# Sensors-V1_1.net
KiCad netlist of a schematic drawn in EAGLE
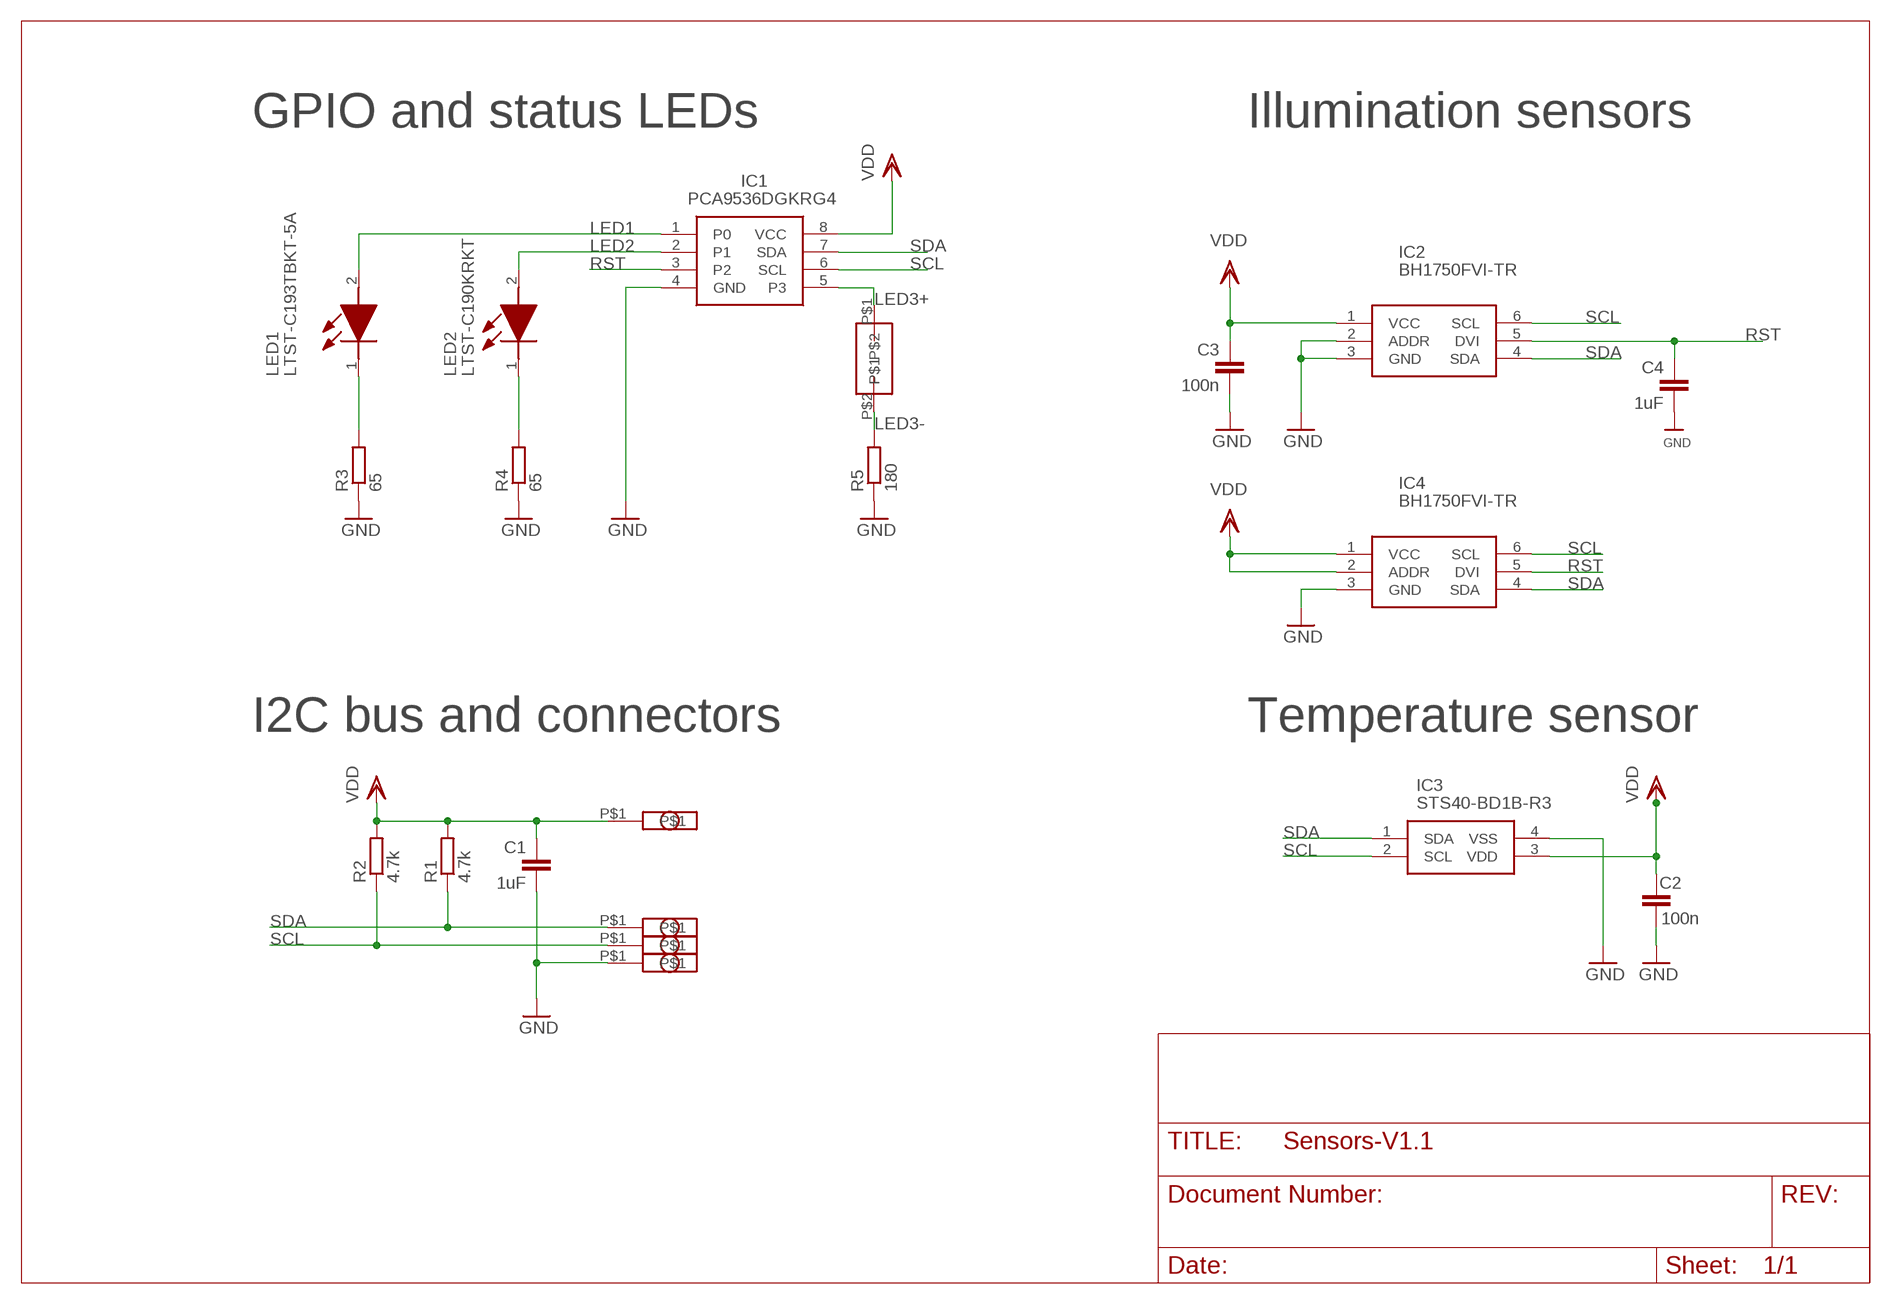
[diagram p0: schematic, sheet 1]

(export (version "E")
  (design (tool "Eeschema 10.0.6"))
  (components
    (comp (ref "C1")
      (value "1uF")
      (footprint "eagle-import:C0603")
      (libsource (lib "eagle-import") (part "C-EUC0603"))
    )
    (comp (ref "C2")
      (value "100n")
      (footprint "eagle-import:C0603")
      (libsource (lib "eagle-import") (part "C-EUC0603"))
    )
    (comp (ref "C3")
      (value "100n")
      (footprint "eagle-import:C0603")
      (libsource (lib "eagle-import") (part "C-EUC0603"))
    )
    (comp (ref "C4")
      (value "1uF")
      (footprint "eagle-import:C0603")
      (libsource (lib "eagle-import") (part "C-EUC0603"))
    )
    (comp (ref "IC1")
      (value "PCA9536DGKRG4")
      (footprint "eagle-import:SOP65P490X110-8N")
      (fields (field (name "MOUSER_PART_NUMBER") "595-PCA9536DGKRG4"))
      (libsource (lib "eagle-import") (part "PCA9536DGKRG4"))
    )
    (comp (ref "IC2")
      (value "BH1750FVI-TR")
      (footprint "eagle-import:WSOF6")
      (libsource (lib "eagle-import") (part "BH1750FVI-TR"))
    )
    (comp (ref "IC3")
      (value "STS40-BD1B-R3")
      (footprint "eagle-import:STS40BD1BR3")
      (fields (field (name "MOUSER_PART_NUMBER") "403-STS40-BD1B-R3"))
      (libsource (lib "eagle-import") (part "STS40-BD1B-R3"))
    )
    (comp (ref "IC4")
      (value "BH1750FVI-TR")
      (footprint "eagle-import:WSOF6")
      (libsource (lib "eagle-import") (part "BH1750FVI-TR"))
    )
    (comp (ref "LED1")
      (value "LTST-C193TBKT-5A")
      (footprint "eagle-import:LEDC1608X45N")
      (fields (field (name "MOUSER_PART_NUMBER") "859-LTSTC193TBKT5A"))
      (libsource (lib "eagle-import") (part "LTST-C193TBKT-5A"))
    )
    (comp (ref "LED2")
      (value "LTST-C190KRKT")
      (footprint "eagle-import:LEDC1607X80N")
      (fields
        (field (name "MANUFACTURER_PART_NUMBER") "LTST-C190KFKT")
        (field (name "MOUSER_PART_NUMBER") "859-LTST-C190KFKT")
      )
      (libsource (lib "eagle-import") (part "LTST-C190KFKT"))
    )
    (comp (ref "R1")
      (value "4.7k")
      (footprint "eagle-import:R0603")
      (libsource (lib "eagle-import") (part "R_JLMR0603"))
    )
    (comp (ref "R2")
      (value "4.7k")
      (footprint "eagle-import:R0603")
      (libsource (lib "eagle-import") (part "R_JLMR0603"))
    )
    (comp (ref "R3")
      (value "65")
      (footprint "eagle-import:R0603")
      (libsource (lib "eagle-import") (part "R_JLMR0603"))
    )
    (comp (ref "R4")
      (value "65")
      (footprint "eagle-import:R0603")
      (libsource (lib "eagle-import") (part "R_JLMR0603"))
    )
    (comp (ref "R5")
      (value "180")
      (footprint "eagle-import:R0603")
      (libsource (lib "eagle-import") (part "R_JLMR0603"))
    )
    (comp (ref "U$1")
      (value "PADL8")
      (footprint "eagle-import:PAD-8")
      (libsource (lib "eagle-import") (part "PADL8"))
    )
    (comp (ref "U$2")
      (value "PADL8")
      (footprint "eagle-import:PAD-8")
      (libsource (lib "eagle-import") (part "PADL8"))
    )
    (comp (ref "U$3")
      (value "PADL8")
      (footprint "eagle-import:PAD-8")
      (libsource (lib "eagle-import") (part "PADL8"))
    )
    (comp (ref "U$4")
      (value "PADL8")
      (footprint "eagle-import:PAD-8")
      (libsource (lib "eagle-import") (part "PADL8"))
    )
    (comp (ref "U$5")
      (value "LEDPINS")
      (footprint "eagle-import:LEDPINS254")
      (libsource (lib "eagle-import") (part "LEDPINS"))
    )
  )
  (nets
    (net (code "1") (name "/LED1") (class "Default")
      (node (ref "IC1") (pin "1") (pinfunction "P0_1") (pintype "bidirectional"))
      (node (ref "LED1") (pin "2") (pinfunction "A_2") (pintype "bidirectional"))
    )
    (net (code "2") (name "/LED2") (class "Default")
      (node (ref "IC1") (pin "2") (pinfunction "P1_2") (pintype "bidirectional"))
      (node (ref "LED2") (pin "2") (pinfunction "A_2") (pintype "bidirectional"))
    )
    (net (code "3") (name "/LED3+") (class "Default")
      (node (ref "IC1") (pin "5") (pinfunction "P3_5") (pintype "bidirectional"))
      (node (ref "U$5") (pin "P$1") (pinfunction "P$1_P$1") (pintype "bidirectional"))
    )
    (net (code "4") (name "/LED3-") (class "Default")
      (node (ref "R5") (pin "2") (pinfunction "2_2") (pintype "passive"))
      (node (ref "U$5") (pin "P$2") (pinfunction "P$2_P$2") (pintype "bidirectional"))
    )
    (net (code "5") (name "/RST") (class "Default")
      (node (ref "C4") (pin "1") (pinfunction "1_1") (pintype "passive"))
      (node (ref "IC1") (pin "3") (pinfunction "P2_3") (pintype "bidirectional"))
      (node (ref "IC2") (pin "5") (pinfunction "DVI_5") (pintype "bidirectional"))
      (node (ref "IC4") (pin "5") (pinfunction "DVI_5") (pintype "bidirectional"))
    )
    (net (code "6") (name "/SCL") (class "Default")
      (node (ref "IC1") (pin "6") (pinfunction "SCL_6") (pintype "bidirectional"))
      (node (ref "IC2") (pin "6") (pinfunction "SCL_6") (pintype "bidirectional"))
      (node (ref "IC3") (pin "2") (pinfunction "SCL_2") (pintype "bidirectional"))
      (node (ref "IC4") (pin "6") (pinfunction "SCL_6") (pintype "bidirectional"))
      (node (ref "R2") (pin "1") (pinfunction "1_1") (pintype "passive"))
      (node (ref "U$2") (pin "P$1") (pinfunction "P$1_P$1") (pintype "bidirectional"))
    )
    (net (code "7") (name "/SDA") (class "Default")
      (node (ref "IC1") (pin "7") (pinfunction "SDA_7") (pintype "bidirectional"))
      (node (ref "IC2") (pin "4") (pinfunction "SDA_4") (pintype "bidirectional"))
      (node (ref "IC3") (pin "1") (pinfunction "SDA_1") (pintype "bidirectional"))
      (node (ref "IC4") (pin "4") (pinfunction "SDA_4") (pintype "bidirectional"))
      (node (ref "R1") (pin "1") (pinfunction "1_1") (pintype "passive"))
      (node (ref "U$1") (pin "P$1") (pinfunction "P$1_P$1") (pintype "bidirectional"))
    )
    (net (code "8") (name "GND") (class "Default")
      (node (ref "C1") (pin "2") (pinfunction "2_2") (pintype "passive"))
      (node (ref "C2") (pin "2") (pinfunction "2_2") (pintype "passive"))
      (node (ref "C3") (pin "2") (pinfunction "2_2") (pintype "passive"))
      (node (ref "C4") (pin "2") (pinfunction "2_2") (pintype "passive"))
      (node (ref "IC1") (pin "4") (pinfunction "GND_4") (pintype "bidirectional"))
      (node (ref "IC2") (pin "2") (pinfunction "ADDR_2") (pintype "bidirectional"))
      (node (ref "IC2") (pin "3") (pinfunction "GND_3") (pintype "bidirectional"))
      (node (ref "IC3") (pin "4") (pinfunction "VSS_4") (pintype "bidirectional"))
      (node (ref "IC4") (pin "3") (pinfunction "GND_3") (pintype "bidirectional"))
      (node (ref "R3") (pin "1") (pinfunction "1_1") (pintype "passive"))
      (node (ref "R4") (pin "1") (pinfunction "1_1") (pintype "passive"))
      (node (ref "R5") (pin "1") (pinfunction "1_1") (pintype "passive"))
      (node (ref "U$3") (pin "P$1") (pinfunction "P$1_P$1") (pintype "bidirectional"))
    )
    (net (code "9") (name "Net-(LED1-K)") (class "Default")
      (node (ref "LED1") (pin "1") (pinfunction "K_1") (pintype "bidirectional"))
      (node (ref "R3") (pin "2") (pinfunction "2_2") (pintype "passive"))
    )
    (net (code "10") (name "Net-(LED2-K)") (class "Default")
      (node (ref "LED2") (pin "1") (pinfunction "K_1") (pintype "bidirectional"))
      (node (ref "R4") (pin "2") (pinfunction "2_2") (pintype "passive"))
    )
    (net (code "11") (name "VDD") (class "Default")
      (node (ref "C1") (pin "1") (pinfunction "1_1") (pintype "passive"))
      (node (ref "C2") (pin "1") (pinfunction "1_1") (pintype "passive"))
      (node (ref "C3") (pin "1") (pinfunction "1_1") (pintype "passive"))
      (node (ref "IC1") (pin "8") (pinfunction "VCC_8") (pintype "bidirectional"))
      (node (ref "IC2") (pin "1") (pinfunction "VCC_1") (pintype "bidirectional"))
      (node (ref "IC3") (pin "3") (pinfunction "VDD_3") (pintype "bidirectional"))
      (node (ref "IC4") (pin "1") (pinfunction "VCC_1") (pintype "bidirectional"))
      (node (ref "IC4") (pin "2") (pinfunction "ADDR_2") (pintype "bidirectional"))
      (node (ref "R1") (pin "2") (pinfunction "2_2") (pintype "passive"))
      (node (ref "R2") (pin "2") (pinfunction "2_2") (pintype "passive"))
      (node (ref "U$4") (pin "P$1") (pinfunction "P$1_P$1") (pintype "bidirectional"))
    )
  )
)
